# schema_esp01-doma.net
KiCad netlist of a schematic drawn in EAGLE
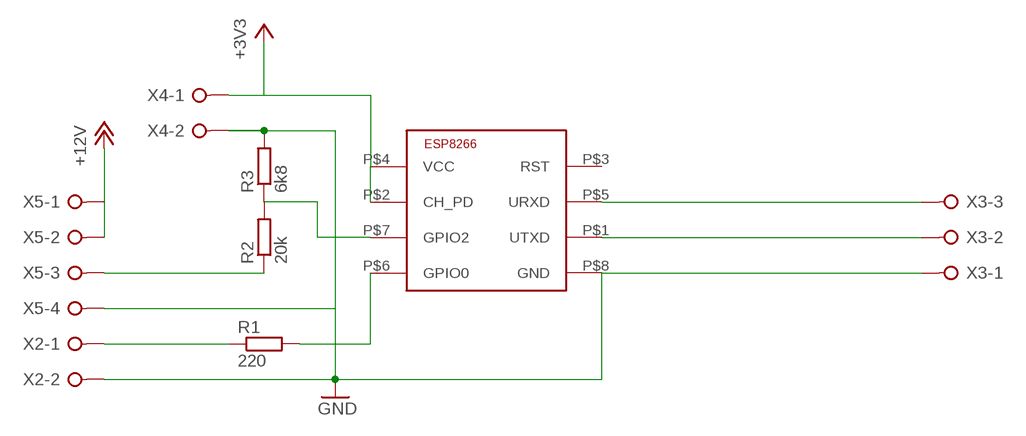
[diagram p0: schematic, sheet 1]

(export (version "E")
  (design (tool "Eeschema 10.0.6"))
  (components
    (comp (ref "R1")
      (value "220")
      (footprint "eagle-import:0204_7")
      (libsource (lib "eagle-import") (part "R-EU_0204/7"))
    )
    (comp (ref "R2")
      (value "20k")
      (footprint "eagle-import:0204_7")
      (libsource (lib "eagle-import") (part "R-EU_0204/7"))
    )
    (comp (ref "R3")
      (value "6k8")
      (footprint "eagle-import:0204_7")
      (libsource (lib "eagle-import") (part "R-EU_0204/7"))
    )
    (comp (ref "U$1")
      (value "ESP8266-01")
      (footprint "eagle-import:ESP-01")
      (libsource (lib "eagle-import") (part "ESP8266-01"))
    )
    (comp (ref "X2")
      (value "W237-02P")
      (footprint "eagle-import:W237-132")
      (libsource (lib "eagle-import") (part "W237-02P"))
    )
    (comp (ref "X3")
      (value "W237-3E")
      (footprint "eagle-import:W237-3E")
      (libsource (lib "eagle-import") (part "W237-3E"))
    )
    (comp (ref "X4")
      (value "W237-02P")
      (footprint "eagle-import:W237-132")
      (libsource (lib "eagle-import") (part "W237-02P"))
    )
    (comp (ref "X5")
      (value "W237-04P")
      (footprint "eagle-import:W237-4P")
      (libsource (lib "eagle-import") (part "W237-04P"))
    )
  )
  (nets
    (net (code "1") (name "+3V3") (class "Default")
      (node (ref "U$1") (pin "P$2") (pinfunction "CH_PD_P$2") (pintype "bidirectional"))
      (node (ref "U$1") (pin "P$4") (pinfunction "VCC_P$4") (pintype "bidirectional"))
      (node (ref "X4") (pin "1") (pinfunction "KL_1") (pintype "passive"))
    )
    (net (code "2") (name "+12V") (class "Default")
      (node (ref "X5") (pin "1") (pinfunction "KL_1") (pintype "passive"))
      (node (ref "X5") (pin "2") (pinfunction "KL_2") (pintype "passive"))
    )
    (net (code "3") (name "GND") (class "Default")
      (node (ref "R3") (pin "2") (pinfunction "2_2") (pintype "passive"))
      (node (ref "U$1") (pin "P$8") (pinfunction "GND_P$8") (pintype "bidirectional"))
      (node (ref "X2") (pin "2") (pinfunction "KL_2") (pintype "passive"))
      (node (ref "X3") (pin "1") (pinfunction "KL_1") (pintype "passive"))
      (node (ref "X4") (pin "2") (pinfunction "KL_2") (pintype "passive"))
      (node (ref "X5") (pin "4") (pinfunction "KL_4") (pintype "passive"))
    )
    (net (code "4") (name "Net-(U$1-GPIO0)") (class "Default")
      (node (ref "R1") (pin "2") (pinfunction "2_2") (pintype "passive"))
      (node (ref "U$1") (pin "P$6") (pinfunction "GPIO0_P$6") (pintype "bidirectional"))
    )
    (net (code "5") (name "Net-(U$1-GPIO2)") (class "Default")
      (node (ref "R2") (pin "2") (pinfunction "2_2") (pintype "passive"))
      (node (ref "R3") (pin "1") (pinfunction "1_1") (pintype "passive"))
      (node (ref "U$1") (pin "P$7") (pinfunction "GPIO2_P$7") (pintype "bidirectional"))
    )
    (net (code "6") (name "Net-(U$1-URXD)") (class "Default")
      (node (ref "U$1") (pin "P$5") (pinfunction "URXD_P$5") (pintype "bidirectional"))
      (node (ref "X3") (pin "3") (pinfunction "KL_3") (pintype "passive"))
    )
    (net (code "7") (name "Net-(U$1-UTXD)") (class "Default")
      (node (ref "U$1") (pin "P$1") (pinfunction "UTXD_P$1") (pintype "bidirectional"))
      (node (ref "X3") (pin "2") (pinfunction "KL_2") (pintype "passive"))
    )
    (net (code "8") (name "Net-(X2A-KL)") (class "Default")
      (node (ref "R1") (pin "1") (pinfunction "1_1") (pintype "passive"))
      (node (ref "X2") (pin "1") (pinfunction "KL_1") (pintype "passive"))
    )
    (net (code "9") (name "Net-(X5C-KL)") (class "Default")
      (node (ref "R2") (pin "1") (pinfunction "1_1") (pintype "passive"))
      (node (ref "X5") (pin "3") (pinfunction "KL_3") (pintype "passive"))
    )
    (net (code "10") (name "unconnected-(U$1-RST-PadP$3)") (class "Default")
      (node (ref "U$1") (pin "P$3") (pinfunction "RST_P$3") (pintype "bidirectional"))
    )
  )
)
